# Adafruit_Feather_RP2040_RFM.net
KiCad netlist of a schematic drawn in EAGLE
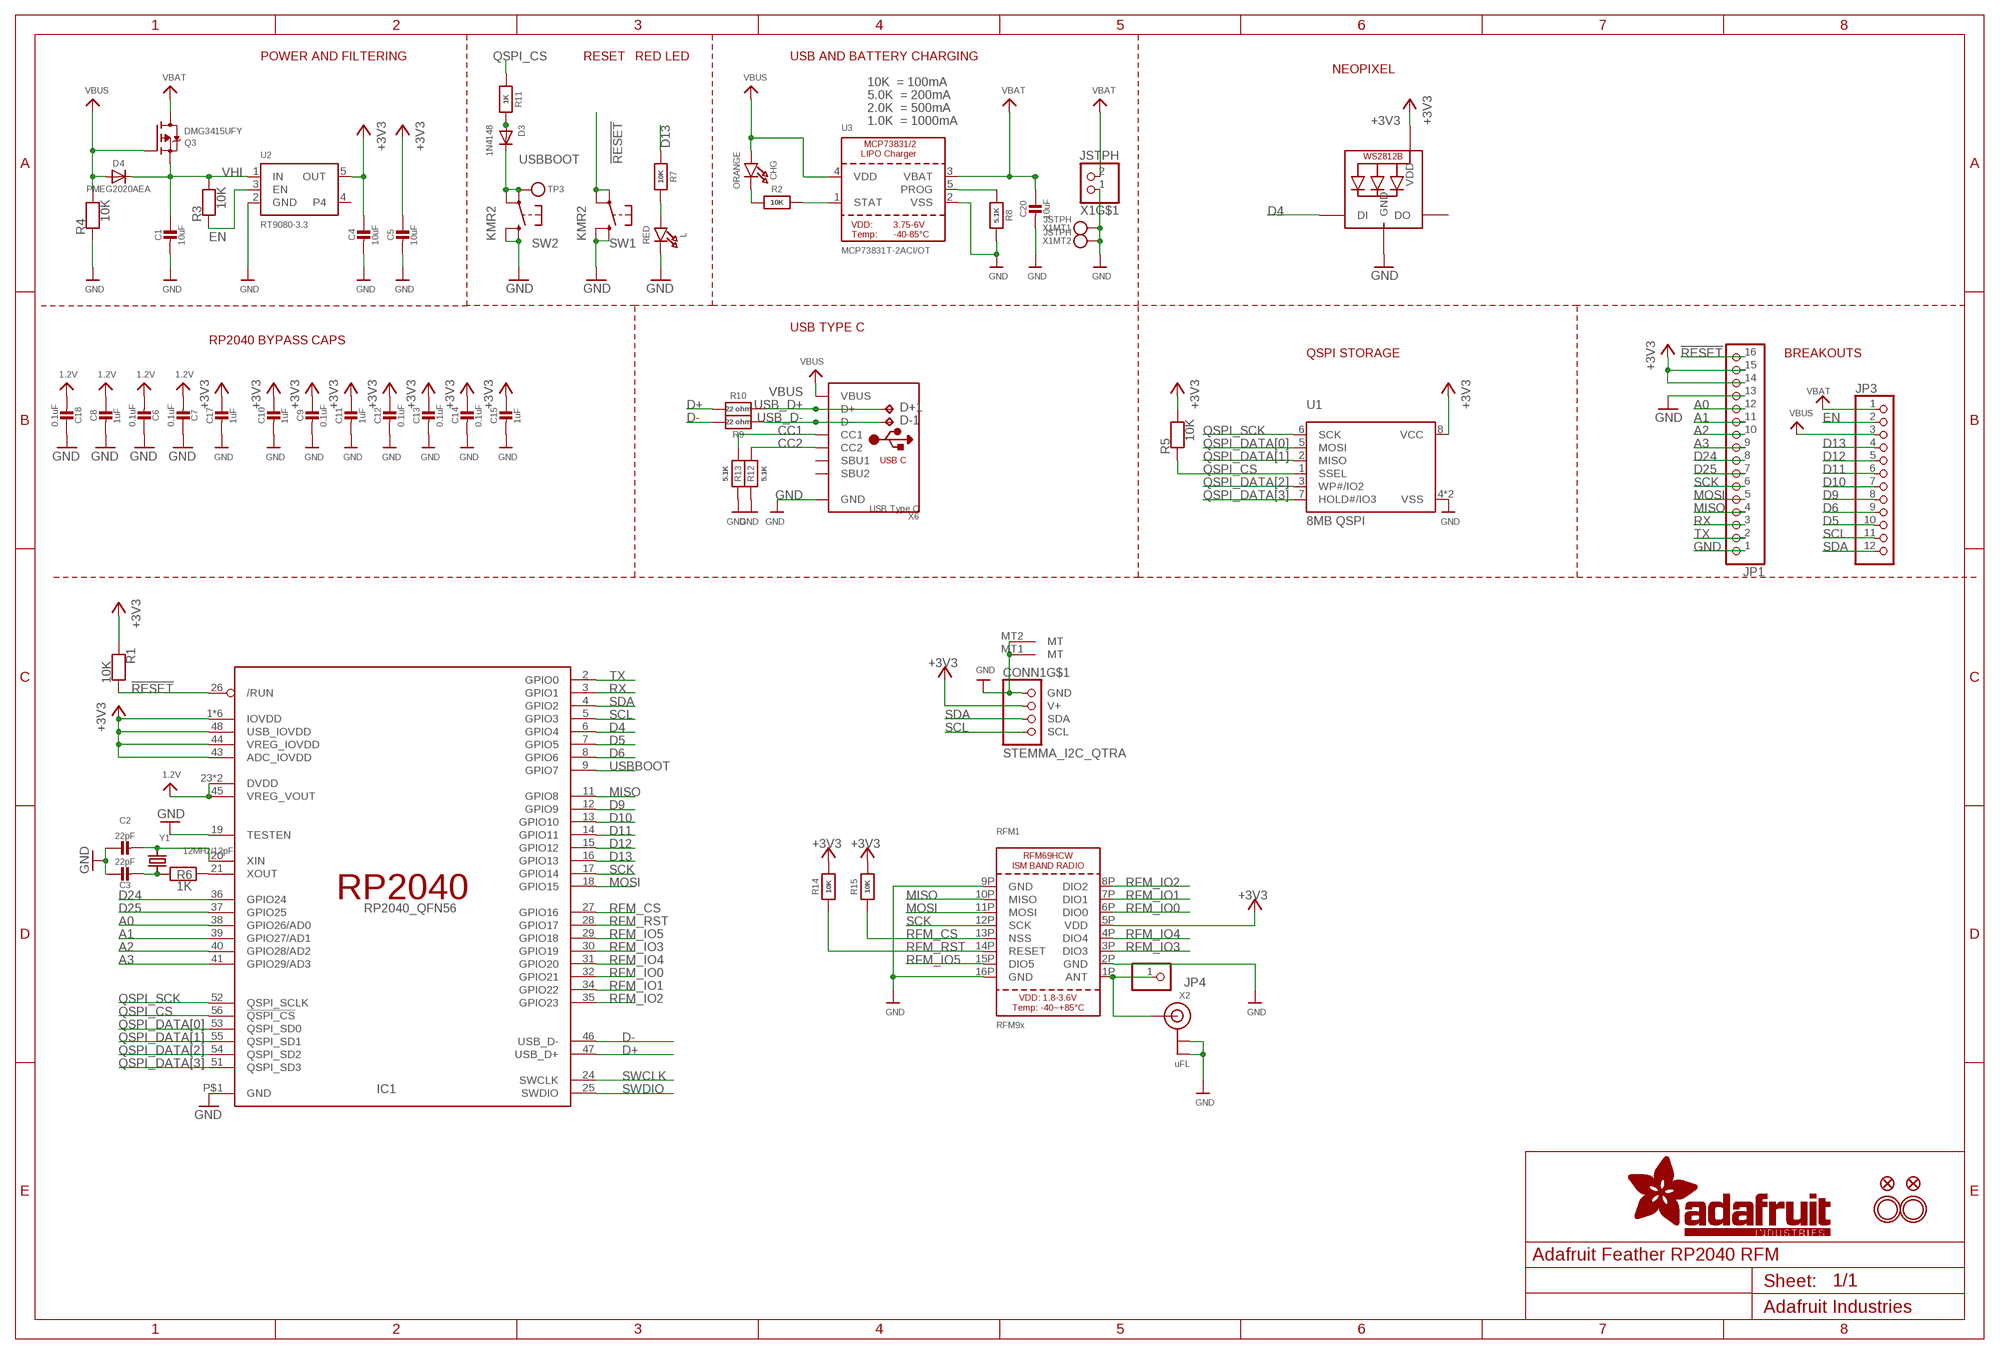
[diagram p0: schematic, sheet 1]

(export (version "E")
  (design (tool "Eeschema 10.0.6"))
  (components
    (comp (ref "C1")
      (value "10uF")
      (footprint "eagle-import:0805-NO")
      (libsource (lib "eagle-import") (part "CAP_CERAMIC0805-NOOUTLINE"))
    )
    (comp (ref "C2")
      (value "22pF")
      (footprint "eagle-import:_0402NO")
      (libsource (lib "eagle-import") (part "CAP_CERAMIC_0402NO"))
    )
    (comp (ref "C3")
      (value "22pF")
      (footprint "eagle-import:_0402NO")
      (libsource (lib "eagle-import") (part "CAP_CERAMIC_0402NO"))
    )
    (comp (ref "C4")
      (value "10uF")
      (footprint "eagle-import:0805-NO")
      (fields (field (name "REV") "A"))
      (libsource (lib "eagle-import") (part "CAP_CERAMIC0805-NOOUTLINE"))
    )
    (comp (ref "C5")
      (value "10uF")
      (footprint "eagle-import:0805-NO")
      (libsource (lib "eagle-import") (part "CAP_CERAMIC0805-NOOUTLINE"))
    )
    (comp (ref "C6")
      (value "0.1uF")
      (footprint "eagle-import:_0402NO")
      (libsource (lib "eagle-import") (part "CAP_CERAMIC_0402NO"))
    )
    (comp (ref "C7")
      (value "0.1uF")
      (footprint "eagle-import:_0402NO")
      (libsource (lib "eagle-import") (part "CAP_CERAMIC_0402NO"))
    )
    (comp (ref "C8")
      (value "1uF")
      (footprint "eagle-import:_0402NO")
      (libsource (lib "eagle-import") (part "CAP_CERAMIC_0402NO"))
    )
    (comp (ref "C9")
      (value "0.1uF")
      (footprint "eagle-import:_0402NO")
      (libsource (lib "eagle-import") (part "CAP_CERAMIC_0402NO"))
    )
    (comp (ref "C10")
      (value "1uF")
      (footprint "eagle-import:_0402NO")
      (libsource (lib "eagle-import") (part "CAP_CERAMIC_0402NO"))
    )
    (comp (ref "C11")
      (value "1uF")
      (footprint "eagle-import:_0402NO")
      (libsource (lib "eagle-import") (part "CAP_CERAMIC_0402NO"))
    )
    (comp (ref "C12")
      (value "0.1uF")
      (footprint "eagle-import:_0402NO")
      (libsource (lib "eagle-import") (part "CAP_CERAMIC_0402NO"))
    )
    (comp (ref "C13")
      (value "0.1uF")
      (footprint "eagle-import:_0402NO")
      (libsource (lib "eagle-import") (part "CAP_CERAMIC_0402NO"))
    )
    (comp (ref "C14")
      (value "0.1uF")
      (footprint "eagle-import:_0402NO")
      (libsource (lib "eagle-import") (part "CAP_CERAMIC_0402NO"))
    )
    (comp (ref "C15")
      (value "1uF")
      (footprint "eagle-import:_0402NO")
      (libsource (lib "eagle-import") (part "CAP_CERAMIC_0402NO"))
    )
    (comp (ref "C17")
      (value "1uF")
      (footprint "eagle-import:_0402NO")
      (libsource (lib "eagle-import") (part "CAP_CERAMIC_0402NO"))
    )
    (comp (ref "C18")
      (value "0.1uF")
      (footprint "eagle-import:_0402NO")
      (libsource (lib "eagle-import") (part "CAP_CERAMIC_0402NO"))
    )
    (comp (ref "C20")
      (value "10uF")
      (footprint "eagle-import:0805-NO")
      (libsource (lib "eagle-import") (part "CAP_CERAMIC0805-NOOUTLINE"))
    )
    (comp (ref "CHG")
      (value "ORANGE")
      (footprint "eagle-import:CHIPLED_0603_NOOUTLINE")
      (libsource (lib "eagle-import") (part "LED0603_NOOUTLINE"))
    )
    (comp (ref "CONN1")
      (value "STEMMA_I2C_QTRA")
      (footprint "eagle-import:JST_SH4_RA")
      (libsource (lib "eagle-import") (part "STEMMA_I2C_QTRA"))
    )
    (comp (ref "D+1")
      (value "TPB1,27")
      (footprint "eagle-import:B1,27")
      (libsource (lib "eagle-import") (part "TPB1,27"))
    )
    (comp (ref "D-1")
      (value "TPB1,27")
      (footprint "eagle-import:B1,27")
      (libsource (lib "eagle-import") (part "TPB1,27"))
    )
    (comp (ref "D3")
      (value "1N4148")
      (footprint "eagle-import:SOD-323F")
      (libsource (lib "eagle-import") (part "DIODESOD-323F"))
    )
    (comp (ref "D4")
      (value "PMEG2020AEA")
      (footprint "eagle-import:SOD-323F")
      (libsource (lib "eagle-import") (part "DIODESOD-323F"))
    )
    (comp (ref "IC1")
      (value "RP2040_QFN56")
      (footprint "eagle-import:QFN56_7MM_REDUCEDEPAD")
      (libsource (lib "eagle-import") (part "RP2040_QFN56"))
    )
    (comp (ref "JP1")
      (value "HEADER-1X16ROUND")
      (footprint "eagle-import:1X16_ROUND")
      (libsource (lib "eagle-import") (part "HEADER-1X16ROUND"))
    )
    (comp (ref "JP3")
      (value "HEADER-1X12")
      (footprint "eagle-import:1X12_ROUND")
      (libsource (lib "eagle-import") (part "HEADER-1X12"))
    )
    (comp (ref "JP4")
      (value "HEADER-1X1ROUND")
      (footprint "eagle-import:1X01_ROUND")
      (libsource (lib "eagle-import") (part "HEADER-1X1ROUND"))
    )
    (comp (ref "L")
      (value "RED")
      (footprint "eagle-import:CHIPLED_0603_NOOUTLINE")
      (libsource (lib "eagle-import") (part "LED0603_NOOUTLINE"))
    )
    (comp (ref "LED1")
      (value "WS2812B_SK6805_1515")
      (footprint "eagle-import:SK6805_1515")
      (libsource (lib "eagle-import") (part "WS2812B_SK6805_1515"))
    )
    (comp (ref "Q3")
      (value "DMG3415UFY")
      (footprint "eagle-import:DFN2015-3")
      (libsource (lib "eagle-import") (part "MOSFET-P_DFN2015"))
    )
    (comp (ref "R1")
      (value "10K")
      (footprint "eagle-import:_0402NO")
      (libsource (lib "eagle-import") (part "RESISTOR_0402NO"))
    )
    (comp (ref "R2")
      (value "10K")
      (footprint "eagle-import:_0402NO")
      (libsource (lib "eagle-import") (part "RESISTOR_0402NO"))
    )
    (comp (ref "R3")
      (value "10K")
      (footprint "eagle-import:_0402NO")
      (libsource (lib "eagle-import") (part "RESISTOR_0402NO"))
    )
    (comp (ref "R4")
      (value "10K")
      (footprint "eagle-import:_0402NO")
      (libsource (lib "eagle-import") (part "RESISTOR_0402NO"))
    )
    (comp (ref "R5")
      (value "10K")
      (footprint "eagle-import:_0402NO")
      (libsource (lib "eagle-import") (part "RESISTOR_0402NO"))
    )
    (comp (ref "R6")
      (value "1K")
      (footprint "eagle-import:_0402NO")
      (libsource (lib "eagle-import") (part "RESISTOR_0402NO"))
    )
    (comp (ref "R7")
      (value "10K")
      (footprint "eagle-import:_0402NO")
      (libsource (lib "eagle-import") (part "RESISTOR_0402NO"))
    )
    (comp (ref "R8")
      (value "5.1K")
      (footprint "eagle-import:_0402NO")
      (libsource (lib "eagle-import") (part "RESISTOR_0402NO"))
    )
    (comp (ref "R9")
      (value "22 ohm")
      (footprint "eagle-import:_0402NO")
      (libsource (lib "eagle-import") (part "RESISTOR_0402NO"))
    )
    (comp (ref "R10")
      (value "22 ohm")
      (footprint "eagle-import:_0402NO")
      (libsource (lib "eagle-import") (part "RESISTOR_0402NO"))
    )
    (comp (ref "R11")
      (value "1K")
      (footprint "eagle-import:_0402NO")
      (libsource (lib "eagle-import") (part "RESISTOR_0402NO"))
    )
    (comp (ref "R12")
      (value "5.1K")
      (footprint "eagle-import:_0402NO")
      (libsource (lib "eagle-import") (part "RESISTOR_0402NO"))
    )
    (comp (ref "R13")
      (value "5.1K")
      (footprint "eagle-import:_0402NO")
      (libsource (lib "eagle-import") (part "RESISTOR_0402NO"))
    )
    (comp (ref "R14")
      (value "10K")
      (footprint "eagle-import:_0402NO")
      (libsource (lib "eagle-import") (part "RESISTOR_0402NO"))
    )
    (comp (ref "R15")
      (value "10K")
      (footprint "eagle-import:_0402NO")
      (libsource (lib "eagle-import") (part "RESISTOR_0402NO"))
    )
    (comp (ref "RFM1")
      (value "RFM9x")
      (footprint "eagle-import:RFMHCW_SMT")
      (fields (field (name "ROT") "270"))
      (libsource (lib "eagle-import") (part "RFM69HCW_SMT"))
    )
    (comp (ref "SW1")
      (value "KMR2")
      (footprint "eagle-import:BTN_RKB2_4.6X2.8")
      (libsource (lib "eagle-import") (part "SWITCH_TACT_SMT_RKB2"))
    )
    (comp (ref "SW2")
      (value "KMR2")
      (footprint "eagle-import:BTN_RKB2_4.6X2.8")
      (libsource (lib "eagle-import") (part "SWITCH_TACT_SMT_RKB2"))
    )
    (comp (ref "TP3")
      (value "TESTPOINTROUND1.5MMNO")
      (footprint "eagle-import:TESTPOINT_ROUND_1.5MM_NO")
      (libsource (lib "eagle-import") (part "TESTPOINTROUND1.5MMNO"))
    )
    (comp (ref "U$31")
      (value "MOUNTINGHOLE2.5")
      (footprint "eagle-import:MOUNTINGHOLE_2.5_PLATED")
      (libsource (lib "eagle-import") (part "MOUNTINGHOLE2.5"))
    )
    (comp (ref "U$32")
      (value "MOUNTINGHOLE2.5")
      (footprint "eagle-import:MOUNTINGHOLE_2.5_PLATED")
      (libsource (lib "eagle-import") (part "MOUNTINGHOLE2.5"))
    )
    (comp (ref "U$34")
      (value "FIDUCIAL_1MM")
      (footprint "eagle-import:FIDUCIAL_1MM")
      (libsource (lib "eagle-import") (part "FIDUCIAL_1MM"))
    )
    (comp (ref "U$35")
      (value "FIDUCIAL_1MM")
      (footprint "eagle-import:FIDUCIAL_1MM")
      (libsource (lib "eagle-import") (part "FIDUCIAL_1MM"))
    )
    (comp (ref "U1")
      (value "8MB QSPI")
      (footprint "eagle-import:USON8_4X4")
      (libsource (lib "eagle-import") (part "SPIFLASH_8PIN_4X4"))
    )
    (comp (ref "U2")
      (value "RT9080-3.3")
      (footprint "eagle-import:SOT23-5")
      (fields (field (name "JLC_ROTATION") "0"))
      (libsource (lib "eagle-import") (part "VREG_SOT23-5"))
    )
    (comp (ref "U3")
      (value "MCP73831T-2ACI/OT")
      (footprint "eagle-import:SOT23-5")
      (libsource (lib "eagle-import") (part "MCP73831/2"))
    )
    (comp (ref "X1")
      (value "JSTPH")
      (footprint "eagle-import:JSTPH2_BATT")
      (libsource (lib "eagle-import") (part "CON_JST_PH_2PIN_MT_BATT"))
    )
    (comp (ref "X2")
      (value "uFL")
      (footprint "eagle-import:U.FL")
      (libsource (lib "eagle-import") (part "ANTENNA_U.FL"))
    )
    (comp (ref "X6")
      (value "USB Type C")
      (footprint "eagle-import:USB_C_CUSB31-CFM2AX-01-X")
      (libsource (lib "eagle-import") (part "USB_C"))
    )
    (comp (ref "Y1")
      (value "12MHz/12pF")
      (footprint "eagle-import:CRYSTAL_2.5X2")
      (libsource (lib "eagle-import") (part "CRYSTAL2.5X2.0"))
    )
  )
  (nets
    (net (code "1") (name "+3V3") (class "Default")
      (node (ref "C10") (pin "1") (pinfunction "1_1") (pintype "passive"))
      (node (ref "C11") (pin "1") (pinfunction "1_1") (pintype "passive"))
      (node (ref "C12") (pin "1") (pinfunction "1_1") (pintype "passive"))
      (node (ref "C13") (pin "1") (pinfunction "1_1") (pintype "passive"))
      (node (ref "C14") (pin "1") (pinfunction "1_1") (pintype "passive"))
      (node (ref "C15") (pin "1") (pinfunction "1_1") (pintype "passive"))
      (node (ref "C17") (pin "1") (pinfunction "1_1") (pintype "passive"))
      (node (ref "C4") (pin "1") (pinfunction "1_1") (pintype "passive"))
      (node (ref "C5") (pin "1") (pinfunction "1_1") (pintype "passive"))
      (node (ref "C9") (pin "1") (pinfunction "1_1") (pintype "passive"))
      (node (ref "CONN1") (pin "2") (pinfunction "V+_2") (pintype "passive"))
      (node (ref "IC1") (pin "1") (pinfunction "IOVDD_1") (pintype "power_in"))
      (node (ref "IC1") (pin "10") (pinfunction "IOVDD_10") (pintype "power_in"))
      (node (ref "IC1") (pin "22") (pinfunction "IOVDD_22") (pintype "power_in"))
      (node (ref "IC1") (pin "33") (pinfunction "IOVDD_33") (pintype "power_in"))
      (node (ref "IC1") (pin "42") (pinfunction "IOVDD_42") (pintype "power_in"))
      (node (ref "IC1") (pin "43") (pinfunction "ADC_IOVDD_43") (pintype "power_in"))
      (node (ref "IC1") (pin "44") (pinfunction "VREG_IOVDD_44") (pintype "power_in"))
      (node (ref "IC1") (pin "48") (pinfunction "USB_IOVDD_48") (pintype "power_in"))
      (node (ref "IC1") (pin "49") (pinfunction "IOVDD_49") (pintype "power_in"))
      (node (ref "JP1") (pin "14") (pinfunction "14_14") (pintype "passive"))
      (node (ref "JP1") (pin "15") (pinfunction "15_15") (pintype "passive"))
      (node (ref "LED1") (pin "2") (pinfunction "VDD_2") (pintype "power_in"))
      (node (ref "R1") (pin "1") (pinfunction "1_1") (pintype "passive"))
      (node (ref "R14") (pin "2") (pinfunction "2_2") (pintype "passive"))
      (node (ref "R15") (pin "2") (pinfunction "2_2") (pintype "passive"))
      (node (ref "R5") (pin "2") (pinfunction "2_2") (pintype "passive"))
      (node (ref "RFM1") (pin "5P") (pinfunction "VDD_5P") (pintype "power_in"))
      (node (ref "U1") (pin "8") (pinfunction "VCC_8") (pintype "bidirectional"))
      (node (ref "U2") (pin "5") (pinfunction "OUT_5") (pintype "power_in"))
    )
    (net (code "2") (name "/A0") (class "Default")
      (node (ref "IC1") (pin "38") (pinfunction "GPIO26/AD0_38") (pintype "bidirectional"))
      (node (ref "JP1") (pin "12") (pinfunction "12_12") (pintype "passive"))
    )
    (net (code "3") (name "/A1") (class "Default")
      (node (ref "IC1") (pin "39") (pinfunction "GPIO27/AD1_39") (pintype "bidirectional"))
      (node (ref "JP1") (pin "11") (pinfunction "11_11") (pintype "passive"))
    )
    (net (code "4") (name "/A2") (class "Default")
      (node (ref "IC1") (pin "40") (pinfunction "GPIO28/AD2_40") (pintype "bidirectional"))
      (node (ref "JP1") (pin "10") (pinfunction "10_10") (pintype "passive"))
    )
    (net (code "5") (name "/A3") (class "Default")
      (node (ref "IC1") (pin "41") (pinfunction "GPIO29/AD3_41") (pintype "bidirectional"))
      (node (ref "JP1") (pin "9") (pinfunction "9_9") (pintype "passive"))
    )
    (net (code "6") (name "/CC1") (class "Default")
      (node (ref "R13") (pin "2") (pinfunction "2_2") (pintype "passive"))
      (node (ref "X6") (pin "A5") (pinfunction "CC1_A5") (pintype "bidirectional"))
    )
    (net (code "7") (name "/CC2") (class "Default")
      (node (ref "R12") (pin "2") (pinfunction "2_2") (pintype "passive"))
      (node (ref "X6") (pin "B5") (pinfunction "CC2_B5") (pintype "bidirectional"))
    )
    (net (code "8") (name "/D+") (class "Default")
      (node (ref "IC1") (pin "47") (pinfunction "USB_D+_47") (pintype "bidirectional"))
      (node (ref "R10") (pin "2") (pinfunction "2_2") (pintype "passive"))
    )
    (net (code "9") (name "/D-") (class "Default")
      (node (ref "IC1") (pin "46") (pinfunction "USB_D-_46") (pintype "bidirectional"))
      (node (ref "R9") (pin "2") (pinfunction "2_2") (pintype "passive"))
    )
    (net (code "10") (name "/D4") (class "Default")
      (node (ref "IC1") (pin "6") (pinfunction "GPIO4_6") (pintype "bidirectional"))
      (node (ref "LED1") (pin "1") (pinfunction "DI_1") (pintype "input"))
    )
    (net (code "11") (name "/D5") (class "Default")
      (node (ref "IC1") (pin "7") (pinfunction "GPIO5_7") (pintype "bidirectional"))
      (node (ref "JP3") (pin "10") (pinfunction "10_10") (pintype "passive"))
    )
    (net (code "12") (name "/D6") (class "Default")
      (node (ref "IC1") (pin "8") (pinfunction "GPIO6_8") (pintype "bidirectional"))
      (node (ref "JP3") (pin "9") (pinfunction "9_9") (pintype "passive"))
    )
    (net (code "13") (name "/D9") (class "Default")
      (node (ref "IC1") (pin "12") (pinfunction "GPIO9_12") (pintype "bidirectional"))
      (node (ref "JP3") (pin "8") (pinfunction "8_8") (pintype "passive"))
    )
    (net (code "14") (name "/D10") (class "Default")
      (node (ref "IC1") (pin "13") (pinfunction "GPIO10_13") (pintype "bidirectional"))
      (node (ref "JP3") (pin "7") (pinfunction "7_7") (pintype "passive"))
    )
    (net (code "15") (name "/D11") (class "Default")
      (node (ref "IC1") (pin "14") (pinfunction "GPIO11_14") (pintype "bidirectional"))
      (node (ref "JP3") (pin "6") (pinfunction "6_6") (pintype "passive"))
    )
    (net (code "16") (name "/D12") (class "Default")
      (node (ref "IC1") (pin "15") (pinfunction "GPIO12_15") (pintype "bidirectional"))
      (node (ref "JP3") (pin "5") (pinfunction "5_5") (pintype "passive"))
    )
    (net (code "17") (name "/D13") (class "Default")
      (node (ref "IC1") (pin "16") (pinfunction "GPIO13_16") (pintype "bidirectional"))
      (node (ref "JP3") (pin "4") (pinfunction "4_4") (pintype "passive"))
      (node (ref "R7") (pin "1") (pinfunction "1_1") (pintype "passive"))
    )
    (net (code "18") (name "/D24") (class "Default")
      (node (ref "IC1") (pin "36") (pinfunction "GPIO24_36") (pintype "bidirectional"))
      (node (ref "JP1") (pin "8") (pinfunction "8_8") (pintype "passive"))
    )
    (net (code "19") (name "/D25") (class "Default")
      (node (ref "IC1") (pin "37") (pinfunction "GPIO25_37") (pintype "bidirectional"))
      (node (ref "JP1") (pin "7") (pinfunction "7_7") (pintype "passive"))
    )
    (net (code "20") (name "/EN") (class "Default")
      (node (ref "JP3") (pin "2") (pinfunction "2_2") (pintype "passive"))
      (node (ref "R3") (pin "1") (pinfunction "1_1") (pintype "passive"))
      (node (ref "U2") (pin "3") (pinfunction "EN_3") (pintype "input"))
    )
    (net (code "21") (name "/MISO") (class "Default")
      (node (ref "IC1") (pin "11") (pinfunction "GPIO8_11") (pintype "bidirectional"))
      (node (ref "JP1") (pin "4") (pinfunction "4_4") (pintype "passive"))
      (node (ref "RFM1") (pin "10P") (pinfunction "MISO_10P") (pintype "output"))
    )
    (net (code "22") (name "/MOSI") (class "Default")
      (node (ref "IC1") (pin "18") (pinfunction "GPIO15_18") (pintype "bidirectional"))
      (node (ref "JP1") (pin "5") (pinfunction "5_5") (pintype "passive"))
      (node (ref "RFM1") (pin "11P") (pinfunction "MOSI_11P") (pintype "input"))
    )
    (net (code "23") (name "/QSPI_CS") (class "Default")
      (node (ref "IC1") (pin "56") (pinfunction "~{QSPI_CS}_56") (pintype "bidirectional"))
      (node (ref "R11") (pin "1") (pinfunction "1_1") (pintype "passive"))
      (node (ref "R5") (pin "1") (pinfunction "1_1") (pintype "passive"))
      (node (ref "U1") (pin "1") (pinfunction "SSEL_1") (pintype "bidirectional"))
    )
    (net (code "24") (name "/QSPI_DATA[0]") (class "Default")
      (node (ref "IC1") (pin "53") (pinfunction "QSPI_SD0_53") (pintype "bidirectional"))
      (node (ref "U1") (pin "5") (pinfunction "MOSI_5") (pintype "bidirectional"))
    )
    (net (code "25") (name "/QSPI_DATA[1]") (class "Default")
      (node (ref "IC1") (pin "55") (pinfunction "QSPI_SD1_55") (pintype "bidirectional"))
      (node (ref "U1") (pin "2") (pinfunction "MISO_2") (pintype "bidirectional"))
    )
    (net (code "26") (name "/QSPI_DATA[2]") (class "Default")
      (node (ref "IC1") (pin "54") (pinfunction "QSPI_SD2_54") (pintype "bidirectional"))
      (node (ref "U1") (pin "3") (pinfunction "WP#/IO2_3") (pintype "bidirectional"))
    )
    (net (code "27") (name "/QSPI_DATA[3]") (class "Default")
      (node (ref "IC1") (pin "51") (pinfunction "QSPI_SD3_51") (pintype "bidirectional"))
      (node (ref "U1") (pin "7") (pinfunction "HOLD#/IO3_7") (pintype "bidirectional"))
    )
    (net (code "28") (name "/QSPI_SCK") (class "Default")
      (node (ref "IC1") (pin "52") (pinfunction "QSPI_SCLK_52") (pintype "bidirectional"))
      (node (ref "U1") (pin "6") (pinfunction "SCK_6") (pintype "bidirectional"))
    )
    (net (code "29") (name "/RFM_CS") (class "Default")
      (node (ref "IC1") (pin "27") (pinfunction "GPIO16_27") (pintype "bidirectional"))
      (node (ref "R15") (pin "1") (pinfunction "1_1") (pintype "passive"))
      (node (ref "RFM1") (pin "13P") (pinfunction "NSS_13P") (pintype "input"))
    )
    (net (code "30") (name "/RFM_IO0") (class "Default")
      (node (ref "IC1") (pin "32") (pinfunction "GPIO21_32") (pintype "bidirectional"))
      (node (ref "RFM1") (pin "6P") (pinfunction "DIO0_6P") (pintype "bidirectional"))
    )
    (net (code "31") (name "/RFM_IO1") (class "Default")
      (node (ref "IC1") (pin "34") (pinfunction "GPIO22_34") (pintype "bidirectional"))
      (node (ref "RFM1") (pin "7P") (pinfunction "DIO1_7P") (pintype "bidirectional"))
    )
    (net (code "32") (name "/RFM_IO2") (class "Default")
      (node (ref "IC1") (pin "35") (pinfunction "GPIO23_35") (pintype "bidirectional"))
      (node (ref "RFM1") (pin "8P") (pinfunction "DIO2_8P") (pintype "bidirectional"))
    )
    (net (code "33") (name "/RFM_IO3") (class "Default")
      (node (ref "IC1") (pin "30") (pinfunction "GPIO19_30") (pintype "bidirectional"))
      (node (ref "RFM1") (pin "3P") (pinfunction "DIO3_3P") (pintype "bidirectional"))
    )
    (net (code "34") (name "/RFM_IO4") (class "Default")
      (node (ref "IC1") (pin "31") (pinfunction "GPIO20_31") (pintype "bidirectional"))
      (node (ref "RFM1") (pin "4P") (pinfunction "DIO4_4P") (pintype "bidirectional"))
    )
    (net (code "35") (name "/RFM_IO5") (class "Default")
      (node (ref "IC1") (pin "29") (pinfunction "GPIO18_29") (pintype "bidirectional"))
      (node (ref "RFM1") (pin "15P") (pinfunction "DIO5_15P") (pintype "bidirectional"))
    )
    (net (code "36") (name "/RFM_RST") (class "Default")
      (node (ref "IC1") (pin "28") (pinfunction "GPIO17_28") (pintype "bidirectional"))
      (node (ref "R14") (pin "1") (pinfunction "1_1") (pintype "passive"))
      (node (ref "RFM1") (pin "14P") (pinfunction "RESET_14P") (pintype "input"))
    )
    (net (code "37") (name "/RX") (class "Default")
      (node (ref "IC1") (pin "3") (pinfunction "GPIO1_3") (pintype "bidirectional"))
      (node (ref "JP1") (pin "3") (pinfunction "3_3") (pintype "passive"))
    )
    (net (code "38") (name "/SCK") (class "Default")
      (node (ref "IC1") (pin "17") (pinfunction "GPIO14_17") (pintype "bidirectional"))
      (node (ref "JP1") (pin "6") (pinfunction "6_6") (pintype "passive"))
      (node (ref "RFM1") (pin "12P") (pinfunction "SCK_12P") (pintype "input"))
    )
    (net (code "39") (name "/SCL") (class "Default")
      (node (ref "CONN1") (pin "4") (pinfunction "SCL_4") (pintype "passive"))
      (node (ref "IC1") (pin "5") (pinfunction "GPIO3_5") (pintype "bidirectional"))
      (node (ref "JP3") (pin "11") (pinfunction "11_11") (pintype "passive"))
    )
    (net (code "40") (name "/SDA") (class "Default")
      (node (ref "CONN1") (pin "3") (pinfunction "SDA_3") (pintype "passive"))
      (node (ref "IC1") (pin "4") (pinfunction "GPIO2_4") (pintype "bidirectional"))
      (node (ref "JP3") (pin "12") (pinfunction "12_12") (pintype "passive"))
    )
    (net (code "41") (name "/SWCLK") (class "Default")
      (node (ref "IC1") (pin "24") (pinfunction "SWCLK_24") (pintype "bidirectional"))
    )
    (net (code "42") (name "/SWDIO") (class "Default")
      (node (ref "IC1") (pin "25") (pinfunction "SWDIO_25") (pintype "bidirectional"))
    )
    (net (code "43") (name "/TX") (class "Default")
      (node (ref "IC1") (pin "2") (pinfunction "GPIO0_2") (pintype "bidirectional"))
      (node (ref "JP1") (pin "2") (pinfunction "2_2") (pintype "passive"))
    )
    (net (code "44") (name "/USBBOOT") (class "Default")
      (node (ref "D3") (pin "C") (pinfunction "C_C") (pintype "passive"))
      (node (ref "IC1") (pin "9") (pinfunction "GPIO7_9") (pintype "bidirectional"))
      (node (ref "SW2") (pin "A") (pinfunction "P_A") (pintype "passive"))
      (node (ref "SW2") (pin "A'") (pinfunction "P1_A'") (pintype "passive"))
      (node (ref "TP3") (pin "P$1") (pinfunction "P$1_P$1") (pintype "bidirectional"))
    )
    (net (code "45") (name "/USB_D+") (class "Default")
      (node (ref "D+1") (pin "TP") (pinfunction "TP_TP") (pintype "input"))
      (node (ref "R10") (pin "1") (pinfunction "1_1") (pintype "passive"))
      (node (ref "X6") (pin "A6") (pinfunction "D+_A6") (pintype "bidirectional"))
      (node (ref "X6") (pin "B6") (pinfunction "D+_B6") (pintype "bidirectional"))
    )
    (net (code "46") (name "/USB_D-") (class "Default")
      (node (ref "D-1") (pin "TP") (pinfunction "TP_TP") (pintype "input"))
      (node (ref "R9") (pin "1") (pinfunction "1_1") (pintype "passive"))
      (node (ref "X6") (pin "A7") (pinfunction "D-_A7") (pintype "bidirectional"))
      (node (ref "X6") (pin "B7") (pinfunction "D-_B7") (pintype "bidirectional"))
    )
    (net (code "47") (name "/VHI") (class "Default")
      (node (ref "C1") (pin "1") (pinfunction "1_1") (pintype "passive"))
      (node (ref "D4") (pin "C") (pinfunction "C_C") (pintype "passive"))
      (node (ref "Q3") (pin "2") (pinfunction "S_2") (pintype "passive"))
      (node (ref "R3") (pin "2") (pinfunction "2_2") (pintype "passive"))
      (node (ref "U2") (pin "1") (pinfunction "IN_1") (pintype "power_in"))
    )
    (net (code "48") (name "/~{RESET}") (class "Default")
      (node (ref "IC1") (pin "26") (pinfunction "/RUN_26") (pintype "bidirectional"))
      (node (ref "JP1") (pin "16") (pinfunction "16_16") (pintype "passive"))
      (node (ref "R1") (pin "2") (pinfunction "2_2") (pintype "passive"))
      (node (ref "SW1") (pin "A") (pinfunction "P_A") (pintype "passive"))
      (node (ref "SW1") (pin "A'") (pinfunction "P1_A'") (pintype "passive"))
    )
    (net (code "49") (name "1.2V") (class "Default")
      (node (ref "C18") (pin "2") (pinfunction "2_2") (pintype "passive"))
      (node (ref "C6") (pin "2") (pinfunction "2_2") (pintype "passive"))
      (node (ref "C7") (pin "2") (pinfunction "2_2") (pintype "passive"))
      (node (ref "C8") (pin "1") (pinfunction "1_1") (pintype "passive"))
      (node (ref "IC1") (pin "23") (pinfunction "DVDD_23") (pintype "power_in"))
      (node (ref "IC1") (pin "45") (pinfunction "VREG_VOUT_45") (pintype "power_in"))
      (node (ref "IC1") (pin "50") (pinfunction "DVDD_50") (pintype "power_in"))
    )
    (net (code "50") (name "GND") (class "Default")
      (node (ref "C1") (pin "2") (pinfunction "2_2") (pintype "passive"))
      (node (ref "C10") (pin "2") (pinfunction "2_2") (pintype "passive"))
      (node (ref "C11") (pin "2") (pinfunction "2_2") (pintype "passive"))
      (node (ref "C12") (pin "2") (pinfunction "2_2") (pintype "passive"))
      (node (ref "C13") (pin "2") (pinfunction "2_2") (pintype "passive"))
      (node (ref "C14") (pin "2") (pinfunction "2_2") (pintype "passive"))
      (node (ref "C15") (pin "2") (pinfunction "2_2") (pintype "passive"))
      (node (ref "C17") (pin "2") (pinfunction "2_2") (pintype "passive"))
      (node (ref "C18") (pin "1") (pinfunction "1_1") (pintype "passive"))
      (node (ref "C2") (pin "1") (pinfunction "1_1") (pintype "passive"))
      (node (ref "C20") (pin "2") (pinfunction "2_2") (pintype "passive"))
      (node (ref "C3") (pin "1") (pinfunction "1_1") (pintype "passive"))
      (node (ref "C4") (pin "2") (pinfunction "2_2") (pintype "passive"))
      (node (ref "C5") (pin "2") (pinfunction "2_2") (pintype "passive"))
      (node (ref "C6") (pin "1") (pinfunction "1_1") (pintype "passive"))
      (node (ref "C7") (pin "1") (pinfunction "1_1") (pintype "passive"))
      (node (ref "C8") (pin "2") (pinfunction "2_2") (pintype "passive"))
      (node (ref "C9") (pin "2") (pinfunction "2_2") (pintype "passive"))
      (node (ref "CONN1") (pin "1") (pinfunction "GND_1") (pintype "passive"))
      (node (ref "CONN1") (pin "MT1") (pinfunction "MT_MT1") (pintype "bidirectional"))
      (node (ref "CONN1") (pin "MT2") (pinfunction "MT_MT2") (pintype "bidirectional"))
      (node (ref "IC1") (pin "19") (pinfunction "TESTEN_19") (pintype "input"))
      (node (ref "IC1") (pin "P$1") (pinfunction "GND_P$1") (pintype "power_in"))
      (node (ref "JP1") (pin "1") (pinfunction "1_1") (pintype "passive"))
      (node (ref "JP1") (pin "13") (pinfunction "13_13") (pintype "passive"))
      (node (ref "L") (pin "C") (pinfunction "C_C") (pintype "passive"))
      (node (ref "LED1") (pin "4") (pinfunction "GND_4") (pintype "power_in"))
      (node (ref "R12") (pin "1") (pinfunction "1_1") (pintype "passive"))
      (node (ref "R13") (pin "1") (pinfunction "1_1") (pintype "passive"))
      (node (ref "R4") (pin "1") (pinfunction "1_1") (pintype "passive"))
      (node (ref "R8") (pin "2") (pinfunction "2_2") (pintype "passive"))
      (node (ref "RFM1") (pin "16P") (pinfunction "GND_16P") (pintype "power_in"))
      (node (ref "RFM1") (pin "2P") (pinfunction "GND_2P") (pintype "power_in"))
      (node (ref "RFM1") (pin "9P") (pinfunction "GND_9P") (pintype "power_in"))
      (node (ref "SW1") (pin "B") (pinfunction "S_B") (pintype "passive"))
      (node (ref "SW1") (pin "B'") (pinfunction "S1_B'") (pintype "passive"))
      (node (ref "SW2") (pin "B") (pinfunction "S_B") (pintype "passive"))
      (node (ref "SW2") (pin "B'") (pinfunction "S1_B'") (pintype "passive"))
      (node (ref "U1") (pin "4") (pinfunction "VSS_4") (pintype "bidirectional"))
      (node (ref "U1") (pin "PAD") (pinfunction "VSS_PAD") (pintype "bidirectional"))
      (node (ref "U2") (pin "2") (pinfunction "GND_2") (pintype "power_in"))
      (node (ref "U3") (pin "2") (pinfunction "VSS_2") (pintype "power_in"))
      (node (ref "X1") (pin "1") (pinfunction "1_1") (pintype "passive"))
      (node (ref "X1") (pin "NC1") (pinfunction "P$1_NC1") (pintype "bidirectional"))
      (node (ref "X1") (pin "NC2") (pinfunction "P$1_NC2") (pintype "bidirectional"))
      (node (ref "X2") (pin "1") (pinfunction "GND_1") (pintype "passive"))
      (node (ref "X2") (pin "2") (pinfunction "GND_2") (pintype "passive"))
      (node (ref "X6") (pin "A1B12") (pinfunction "GND_A1B12") (pintype "power_in"))
      (node (ref "X6") (pin "B1A12") (pinfunction "GND_B1A12") (pintype "power_in"))
    )
    (net (code "51") (name "Net-(C3-Pad2)") (class "Default")
      (node (ref "C3") (pin "2") (pinfunction "2_2") (pintype "passive"))
      (node (ref "R6") (pin "1") (pinfunction "1_1") (pintype "passive"))
      (node (ref "Y1") (pin "1") (pinfunction "1_1") (pintype "passive"))
    )
    (net (code "52") (name "Net-(CHG-PadC)") (class "Default")
      (node (ref "CHG") (pin "C") (pinfunction "C_C") (pintype "passive"))
      (node (ref "R2") (pin "1") (pinfunction "1_1") (pintype "passive"))
    )
    (net (code "53") (name "Net-(D3-PadA)") (class "Default")
      (node (ref "D3") (pin "A") (pinfunction "A_A") (pintype "passive"))
      (node (ref "R11") (pin "2") (pinfunction "2_2") (pintype "passive"))
    )
    (net (code "54") (name "Net-(IC1-XIN)") (class "Default")
      (node (ref "C2") (pin "2") (pinfunction "2_2") (pintype "passive"))
      (node (ref "IC1") (pin "20") (pinfunction "XIN_20") (pintype "input"))
      (node (ref "Y1") (pin "3") (pinfunction "2_3") (pintype "passive"))
    )
    (net (code "55") (name "Net-(IC1-XOUT)") (class "Default")
      (node (ref "IC1") (pin "21") (pinfunction "XOUT_21") (pintype "output"))
      (node (ref "R6") (pin "2") (pinfunction "2_2") (pintype "passive"))
    )
    (net (code "56") (name "Net-(L-PadA)") (class "Default")
      (node (ref "L") (pin "A") (pinfunction "A_A") (pintype "passive"))
      (node (ref "R7") (pin "2") (pinfunction "2_2") (pintype "passive"))
    )
    (net (code "57") (name "Net-(RFM1-ANT)") (class "Default")
      (node (ref "JP4") (pin "1") (pinfunction "1_1") (pintype "passive"))
      (node (ref "RFM1") (pin "1P") (pinfunction "ANT_1P") (pintype "bidirectional"))
      (node (ref "X2") (pin "3") (pinfunction "SIGNAL_3") (pintype "passive"))
    )
    (net (code "58") (name "Net-(U3-PROG)") (class "Default")
      (node (ref "R8") (pin "1") (pinfunction "1_1") (pintype "passive"))
      (node (ref "U3") (pin "5") (pinfunction "PROG_5") (pintype "input"))
    )
    (net (code "59") (name "Net-(U3-STAT)") (class "Default")
      (node (ref "R2") (pin "2") (pinfunction "2_2") (pintype "passive"))
      (node (ref "U3") (pin "1") (pinfunction "STAT_1") (pintype "output"))
    )
    (net (code "60") (name "VBAT") (class "Default")
      (node (ref "C20") (pin "1") (pinfunction "1_1") (pintype "passive"))
      (node (ref "JP3") (pin "1") (pinfunction "1_1") (pintype "passive"))
      (node (ref "Q3") (pin "3") (pinfunction "D_3") (pintype "passive"))
      (node (ref "U3") (pin "3") (pinfunction "VBAT_3") (pintype "power_in"))
      (node (ref "X1") (pin "2") (pinfunction "2_2") (pintype "passive"))
    )
    (net (code "61") (name "VBUS") (class "Default")
      (node (ref "CHG") (pin "A") (pinfunction "A_A") (pintype "passive"))
      (node (ref "D4") (pin "A") (pinfunction "A_A") (pintype "passive"))
      (node (ref "JP3") (pin "3") (pinfunction "3_3") (pintype "passive"))
      (node (ref "Q3") (pin "1") (pinfunction "G_1") (pintype "passive"))
      (node (ref "R4") (pin "2") (pinfunction "2_2") (pintype "passive"))
      (node (ref "U3") (pin "4") (pinfunction "VDD_4") (pintype "power_in"))
      (node (ref "X6") (pin "A4B9") (pinfunction "VBUS_A4B9") (pintype "power_in"))
      (node (ref "X6") (pin "B4A9") (pinfunction "VBUS_B4A9") (pintype "power_in"))
    )
    (net (code "62") (name "unconnected-(LED1-DO-Pad3)") (class "Default")
      (node (ref "LED1") (pin "3") (pinfunction "DO_3") (pintype "output"))
    )
    (net (code "63") (name "unconnected-(U2-P4-Pad4)") (class "Default")
      (node (ref "U2") (pin "4") (pinfunction "P4_4") (pintype "bidirectional"))
    )
    (net (code "64") (name "unconnected-(X6-SBU1-PadA8)") (class "Default")
      (node (ref "X6") (pin "A8") (pinfunction "SBU1_A8") (pintype "bidirectional"))
    )
    (net (code "65") (name "unconnected-(X6-SBU2-PadB8)") (class "Default")
      (node (ref "X6") (pin "B8") (pinfunction "SBU2_B8") (pintype "bidirectional"))
    )
  )
)
